# P_ytka_ESPv2.net
KiCad netlist of a schematic drawn in EAGLE
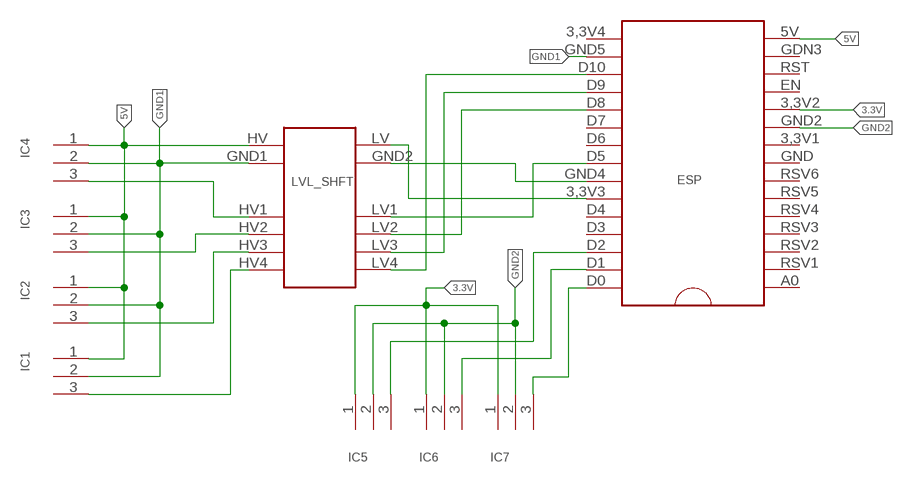
[diagram p0: schematic, sheet 1]

(export (version "E")
  (design (tool "Eeschema 10.0.6"))
  (components
    (comp (ref "ESP")
      (value "ESP8266_NODEMCUV2")
      (footprint "eagle-import:ESP8266_NODEMCV2")
      (libsource (lib "eagle-import") (part "ESP8266_NODEMCUV2"))
    )
    (comp (ref "IC1")
      (value "3,5MM_3PIN")
      (footprint "eagle-import:3,5MM_3PIN")
      (libsource (lib "eagle-import") (part "3,5MM_3PIN"))
    )
    (comp (ref "IC2")
      (value "3,5MM_3PIN")
      (footprint "eagle-import:3,5MM_3PIN")
      (libsource (lib "eagle-import") (part "3,5MM_3PIN"))
    )
    (comp (ref "IC3")
      (value "3,5MM_3PIN")
      (footprint "eagle-import:3,5MM_3PIN")
      (libsource (lib "eagle-import") (part "3,5MM_3PIN"))
    )
    (comp (ref "IC4")
      (value "3,5MM_3PIN")
      (footprint "eagle-import:3,5MM_3PIN")
      (libsource (lib "eagle-import") (part "3,5MM_3PIN"))
    )
    (comp (ref "IC5")
      (value "3,5MM_3PIN")
      (footprint "eagle-import:3,5MM_3PIN")
      (libsource (lib "eagle-import") (part "3,5MM_3PIN"))
    )
    (comp (ref "IC6")
      (value "3,5MM_3PIN")
      (footprint "eagle-import:3,5MM_3PIN")
      (libsource (lib "eagle-import") (part "3,5MM_3PIN"))
    )
    (comp (ref "IC7")
      (value "3,5MM_3PIN")
      (footprint "eagle-import:3,5MM_3PIN")
      (libsource (lib "eagle-import") (part "3,5MM_3PIN"))
    )
    (comp (ref "LVL_SHFT")
      (value "LVL_SHIFTER_4CH")
      (footprint "eagle-import:LVL_SHIFTER_4CH")
      (libsource (lib "eagle-import") (part "LVL_SHIFTER_4CH"))
    )
  )
  (nets
    (net (code "1") (name "3.3V") (class "Default")
      (node (ref "ESP") (pin "3,3V2") (pinfunction "P$11_3,3V2") (pintype "bidirectional"))
      (node (ref "IC5") (pin "1") (pinfunction "P$1_1") (pintype "bidirectional"))
      (node (ref "IC6") (pin "1") (pinfunction "P$1_1") (pintype "bidirectional"))
      (node (ref "IC7") (pin "1") (pinfunction "P$1_1") (pintype "bidirectional"))
    )
    (net (code "2") (name "5V") (class "Default")
      (node (ref "ESP") (pin "5V") (pinfunction "P$15_5V") (pintype "bidirectional"))
      (node (ref "IC1") (pin "1") (pinfunction "P$1_1") (pintype "bidirectional"))
      (node (ref "IC2") (pin "1") (pinfunction "P$1_1") (pintype "bidirectional"))
      (node (ref "IC3") (pin "1") (pinfunction "P$1_1") (pintype "bidirectional"))
      (node (ref "IC4") (pin "1") (pinfunction "P$1_1") (pintype "bidirectional"))
      (node (ref "LVL_SHFT") (pin "HV") (pinfunction "HV_HV") (pintype "bidirectional"))
    )
    (net (code "3") (name "GND1") (class "Default")
      (node (ref "ESP") (pin "GND5") (pinfunction "P$17_GND5") (pintype "bidirectional"))
      (node (ref "IC1") (pin "2") (pinfunction "P$2_2") (pintype "bidirectional"))
      (node (ref "IC2") (pin "2") (pinfunction "P$2_2") (pintype "bidirectional"))
      (node (ref "IC3") (pin "2") (pinfunction "P$2_2") (pintype "bidirectional"))
      (node (ref "IC4") (pin "2") (pinfunction "P$2_2") (pintype "bidirectional"))
      (node (ref "LVL_SHFT") (pin "GND1") (pinfunction "GND1_GND1") (pintype "bidirectional"))
    )
    (net (code "4") (name "GND2") (class "Default")
      (node (ref "ESP") (pin "GND2") (pinfunction "P$10_GND2") (pintype "bidirectional"))
      (node (ref "IC5") (pin "2") (pinfunction "P$2_2") (pintype "bidirectional"))
      (node (ref "IC6") (pin "2") (pinfunction "P$2_2") (pintype "bidirectional"))
      (node (ref "IC7") (pin "2") (pinfunction "P$2_2") (pintype "bidirectional"))
    )
    (net (code "5") (name "Net-(ESP-P$18)") (class "Default")
      (node (ref "ESP") (pin "D10") (pinfunction "P$18_D10") (pintype "bidirectional"))
      (node (ref "LVL_SHFT") (pin "LV4") (pinfunction "LV4_LV4") (pintype "bidirectional"))
    )
    (net (code "6") (name "Net-(ESP-P$19)") (class "Default")
      (node (ref "ESP") (pin "D9") (pinfunction "P$19_D9") (pintype "bidirectional"))
      (node (ref "LVL_SHFT") (pin "LV3") (pinfunction "LV3_LV3") (pintype "bidirectional"))
    )
    (net (code "7") (name "Net-(ESP-P$20)") (class "Default")
      (node (ref "ESP") (pin "D8") (pinfunction "P$20_D8") (pintype "bidirectional"))
      (node (ref "LVL_SHFT") (pin "LV2") (pinfunction "LV2_LV2") (pintype "bidirectional"))
    )
    (net (code "8") (name "Net-(ESP-P$23)") (class "Default")
      (node (ref "ESP") (pin "D5") (pinfunction "P$23_D5") (pintype "bidirectional"))
      (node (ref "LVL_SHFT") (pin "LV1") (pinfunction "LV1_LV1") (pintype "bidirectional"))
    )
    (net (code "9") (name "Net-(ESP-P$24)") (class "Default")
      (node (ref "ESP") (pin "GND4") (pinfunction "P$24_GND4") (pintype "bidirectional"))
      (node (ref "LVL_SHFT") (pin "GND2") (pinfunction "GND2_GND2") (pintype "bidirectional"))
    )
    (net (code "10") (name "Net-(ESP-P$25)") (class "Default")
      (node (ref "ESP") (pin "3,3V3") (pinfunction "P$25_3,3V3") (pintype "bidirectional"))
      (node (ref "LVL_SHFT") (pin "LV") (pinfunction "LV_LV") (pintype "bidirectional"))
    )
    (net (code "11") (name "Net-(ESP-P$28)") (class "Default")
      (node (ref "ESP") (pin "D2") (pinfunction "P$28_D2") (pintype "bidirectional"))
      (node (ref "IC5") (pin "3") (pinfunction "P$3_3") (pintype "bidirectional"))
    )
    (net (code "12") (name "Net-(ESP-P$29)") (class "Default")
      (node (ref "ESP") (pin "D1") (pinfunction "P$29_D1") (pintype "bidirectional"))
      (node (ref "IC6") (pin "3") (pinfunction "P$3_3") (pintype "bidirectional"))
    )
    (net (code "13") (name "Net-(ESP-P$30)") (class "Default")
      (node (ref "ESP") (pin "D0") (pinfunction "P$30_D0") (pintype "bidirectional"))
      (node (ref "IC7") (pin "3") (pinfunction "P$3_3") (pintype "bidirectional"))
    )
    (net (code "14") (name "Net-(IC1-P$3)") (class "Default")
      (node (ref "IC1") (pin "3") (pinfunction "P$3_3") (pintype "bidirectional"))
      (node (ref "LVL_SHFT") (pin "HV4") (pinfunction "HV4_HV4") (pintype "bidirectional"))
    )
    (net (code "15") (name "Net-(IC2-P$3)") (class "Default")
      (node (ref "IC2") (pin "3") (pinfunction "P$3_3") (pintype "bidirectional"))
      (node (ref "LVL_SHFT") (pin "HV3") (pinfunction "HV3_HV3") (pintype "bidirectional"))
    )
    (net (code "16") (name "Net-(IC3-P$3)") (class "Default")
      (node (ref "IC3") (pin "3") (pinfunction "P$3_3") (pintype "bidirectional"))
      (node (ref "LVL_SHFT") (pin "HV2") (pinfunction "HV2_HV2") (pintype "bidirectional"))
    )
    (net (code "17") (name "Net-(IC4-P$3)") (class "Default")
      (node (ref "IC4") (pin "3") (pinfunction "P$3_3") (pintype "bidirectional"))
      (node (ref "LVL_SHFT") (pin "HV1") (pinfunction "HV1_HV1") (pintype "bidirectional"))
    )
    (net (code "18") (name "unconnected-(ESP-P$1-PadA0)") (class "Default")
      (node (ref "ESP") (pin "A0") (pinfunction "P$1_A0") (pintype "bidirectional"))
    )
    (net (code "19") (name "unconnected-(ESP-P$2-PadRSV1)") (class "Default")
      (node (ref "ESP") (pin "RSV1") (pinfunction "P$2_RSV1") (pintype "bidirectional"))
    )
    (net (code "20") (name "unconnected-(ESP-P$3-PadRSV2)") (class "Default")
      (node (ref "ESP") (pin "RSV2") (pinfunction "P$3_RSV2") (pintype "bidirectional"))
    )
    (net (code "21") (name "unconnected-(ESP-P$4-PadRSV3)") (class "Default")
      (node (ref "ESP") (pin "RSV3") (pinfunction "P$4_RSV3") (pintype "bidirectional"))
    )
    (net (code "22") (name "unconnected-(ESP-P$5-PadRSV4)") (class "Default")
      (node (ref "ESP") (pin "RSV4") (pinfunction "P$5_RSV4") (pintype "bidirectional"))
    )
    (net (code "23") (name "unconnected-(ESP-P$6-PadRSV5)") (class "Default")
      (node (ref "ESP") (pin "RSV5") (pinfunction "P$6_RSV5") (pintype "bidirectional"))
    )
    (net (code "24") (name "unconnected-(ESP-P$7-PadRSV6)") (class "Default")
      (node (ref "ESP") (pin "RSV6") (pinfunction "P$7_RSV6") (pintype "bidirectional"))
    )
    (net (code "25") (name "unconnected-(ESP-P$8-PadGND)") (class "Default")
      (node (ref "ESP") (pin "GND") (pinfunction "P$8_GND") (pintype "bidirectional"))
    )
    (net (code "26") (name "unconnected-(ESP-P$9-Pad3,3V1)") (class "Default")
      (node (ref "ESP") (pin "3,3V1") (pinfunction "P$9_3,3V1") (pintype "bidirectional"))
    )
    (net (code "27") (name "unconnected-(ESP-P$12-PadEN)") (class "Default")
      (node (ref "ESP") (pin "EN") (pinfunction "P$12_EN") (pintype "bidirectional"))
    )
    (net (code "28") (name "unconnected-(ESP-P$13-PadRST)") (class "Default")
      (node (ref "ESP") (pin "RST") (pinfunction "P$13_RST") (pintype "bidirectional"))
    )
    (net (code "29") (name "unconnected-(ESP-P$14-PadGDN3)") (class "Default")
      (node (ref "ESP") (pin "GDN3") (pinfunction "P$14_GDN3") (pintype "bidirectional"))
    )
    (net (code "30") (name "unconnected-(ESP-P$16-Pad3,3V4)") (class "Default")
      (node (ref "ESP") (pin "3,3V4") (pinfunction "P$16_3,3V4") (pintype "bidirectional"))
    )
    (net (code "31") (name "unconnected-(ESP-P$21-PadD7)") (class "Default")
      (node (ref "ESP") (pin "D7") (pinfunction "P$21_D7") (pintype "bidirectional"))
    )
    (net (code "32") (name "unconnected-(ESP-P$22-PadD6)") (class "Default")
      (node (ref "ESP") (pin "D6") (pinfunction "P$22_D6") (pintype "bidirectional"))
    )
    (net (code "33") (name "unconnected-(ESP-P$26-PadD4)") (class "Default")
      (node (ref "ESP") (pin "D4") (pinfunction "P$26_D4") (pintype "bidirectional"))
    )
    (net (code "34") (name "unconnected-(ESP-P$27-PadD3)") (class "Default")
      (node (ref "ESP") (pin "D3") (pinfunction "P$27_D3") (pintype "bidirectional"))
    )
  )
)
